# LowPassFilter.net
KiCad netlist of a schematic drawn in Altium Designer
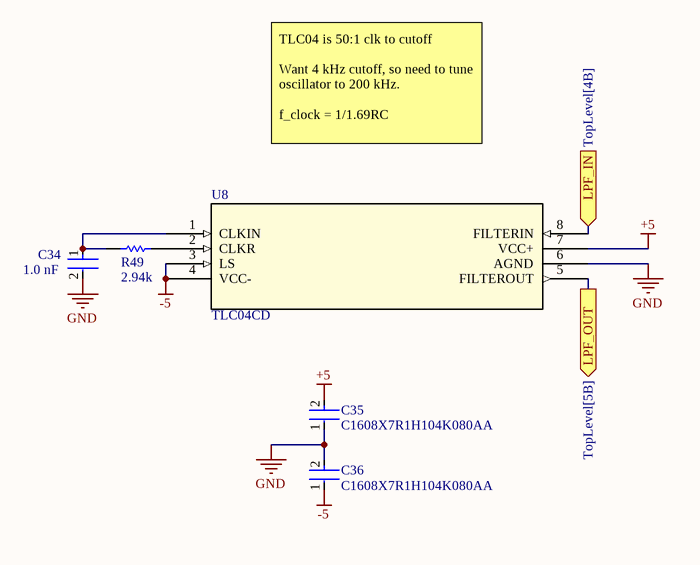
[diagram p0: LowPassFilter.SchDoc]

(export (version "E")
  (design (tool "Eeschema 10.0.6"))
  (components
    (comp (ref "C34")
      (value "CC0603KRX7R9BB102")
      (footprint "FP-CC0603-DA-MFG")
      (description "CAP CER 1000PF 50V X7R 0603")
      (fields
        (field (name "MANUFACTURER") "YAGEO")
        (field (name "CAPACITANCE") "1.0 nF")
        (field (name "OCTOPART") "https://octopart.com/cc0603krx7r9bb102-yageo-192933")
      )
      (libsource (lib "Altium Content Vault") (part "11868f565c42a9108669ba33697ecf6"))
    )
    (comp (ref "C35")
      (value "C1608X7R1H104K080AA")
      (footprint "FP-C1608-080-0_1-MFG")
      (description "Multilayer Ceramic Capacitors 100nF ±10% 50V X7R SMD 0603")
      (fields (field (name "VOLTAGE") "50V") (field (name "TOLERANCE") "10%"))
      (libsource (lib "Altium Content Vault") (part "236180d848d6139a670b325ea6854c9"))
    )
    (comp (ref "C36")
      (value "C1608X7R1H104K080AA")
      (footprint "FP-C1608-080-0_1-MFG")
      (description "Multilayer Ceramic Capacitors 100nF ±10% 50V X7R SMD 0603")
      (fields (field (name "VOLTAGE") "50V") (field (name "TOLERANCE") "10%"))
      (libsource (lib "Altium Content Vault") (part "236180d848d6139a670b325ea6854c9"))
    )
    (comp (ref "R49")
      (value "RC0603FR-072K94L")
      (footprint "RESC1608X55X25ML10T15")
      (fields (field (name "MANUFACTURER") "Yageo") (field (name "RESISTANCE") "2.94k"))
      (libsource (lib "Altium Content Vault") (part "RES"))
    )
    (comp (ref "U8")
      (value "TLC04CD")
      (footprint "D8")
      (description "No Description Available")
      (libsource (lib "TLC04CD") (part "TLC04CD"))
    )
  )
  (nets
    (net (code "1") (name "+5") (class "Default")
      (node (ref "C35") (pin "2") (pinfunction "2_2") (pintype "passive"))
      (node (ref "U8") (pin "7") (pinfunction "VCC+_7") (pintype "power_in"))
    )
    (net (code "2") (name "-5") (class "Default")
      (node (ref "C36") (pin "1") (pinfunction "1_1") (pintype "passive"))
      (node (ref "U8") (pin "3") (pinfunction "LS_3") (pintype "input"))
      (node (ref "U8") (pin "4") (pinfunction "VCC-_4") (pintype "power_in"))
    )
    (net (code "3") (name "/LPF_IN") (class "Default")
      (node (ref "U8") (pin "8") (pinfunction "FILTERIN_8") (pintype "input"))
    )
    (net (code "4") (name "/LPF_OUT") (class "Default")
      (node (ref "U8") (pin "5") (pinfunction "FILTEROUT_5") (pintype "output"))
    )
    (net (code "5") (name "GND") (class "Default")
      (node (ref "C34") (pin "2") (pinfunction "2_2") (pintype "passive"))
      (node (ref "C35") (pin "1") (pinfunction "1_1") (pintype "passive"))
      (node (ref "C36") (pin "2") (pinfunction "2_2") (pintype "passive"))
      (node (ref "U8") (pin "6") (pinfunction "AGND_6") (pintype "power_in"))
    )
    (net (code "6") (name "Net-(U8-CLKIN)") (class "Default")
      (node (ref "C34") (pin "1") (pinfunction "1_1") (pintype "passive"))
      (node (ref "R49") (pin "1") (pinfunction "1_1") (pintype "passive"))
      (node (ref "U8") (pin "1") (pinfunction "CLKIN_1") (pintype "input"))
    )
    (net (code "7") (name "Net-(U8-CLKR)") (class "Default")
      (node (ref "R49") (pin "2") (pinfunction "2_2") (pintype "passive"))
      (node (ref "U8") (pin "2") (pinfunction "CLKR_2") (pintype "input"))
    )
  )
)
